# dc-breakout-board.net
KiCad netlist of a schematic drawn in Altium Designer
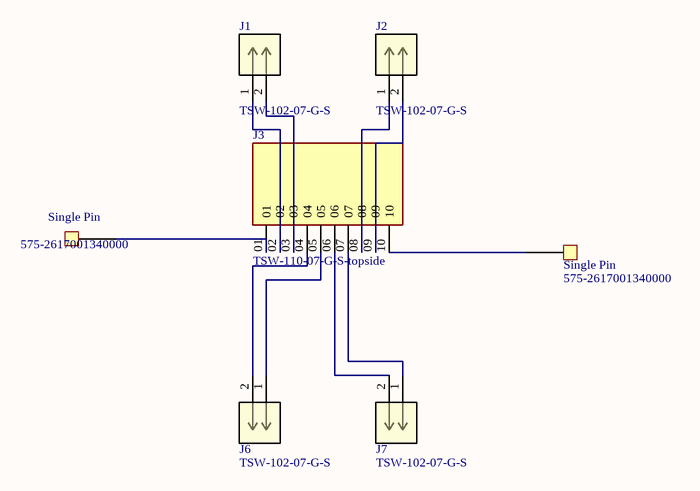
[diagram p0: dc-breakout-board.SchDoc]

(export (version "E")
  (design (tool "Eeschema 10.0.6"))
  (components
    (comp (ref "J1")
      (value "TSW-102-07-G-S")
      (footprint "TSW-102-07-G-S-iceberg")
      (description "No Description Available")
      (fields (field (name "COPYRIGHT") "Copyright (C) 2024 Ultra Librarian. All rights reserved."))
      (libsource (lib "SchlibLafe") (part "TSW-102-07-G-S-iceberg"))
    )
    (comp (ref "J2")
      (value "TSW-102-07-G-S")
      (footprint "TSW-102-07-G-S-iceberg")
      (description "No Description Available")
      (fields (field (name "COPYRIGHT") "Copyright (C) 2024 Ultra Librarian. All rights reserved."))
      (libsource (lib "SchlibLafe") (part "TSW-102-07-G-S-iceberg"))
    )
    (comp (ref "J3")
      (value "TSW-110-07-G-S-topside")
      (footprint "SAMTEC_TSW-110-07-G-S")
      (fields (field (name "MF") "Samtec Inc.") (field (name "MP") "TSW-110-07-G-S"))
      (libsource (lib "SchlibLafe") (part "TSW-110-07-G-S-topside"))
    )
    (comp (ref "J4")
      (value "Single Pin")
      (footprint "Single PC Pin")
      (fields (field (name "SUPPLIER PART NUMBER 1") "575-2617001340000"))
      (libsource (lib "SchlibLafe") (part "Single PC Pin"))
    )
    (comp (ref "J5")
      (value "Single Pin")
      (footprint "Single PC Pin")
      (fields (field (name "SUPPLIER PART NUMBER 1") "575-2617001340000"))
      (libsource (lib "") (part "Single PC Pin_1"))
    )
    (comp (ref "J6")
      (value "TSW-102-07-G-S")
      (footprint "TSW-102-07-G-S-iceberg")
      (description "No Description Available")
      (fields (field (name "COPYRIGHT") "Copyright (C) 2024 Ultra Librarian. All rights reserved."))
      (libsource (lib "") (part "TSW-102-07-G-S-iceberg_1"))
    )
    (comp (ref "J7")
      (value "TSW-102-07-G-S")
      (footprint "TSW-102-07-G-S-iceberg")
      (description "No Description Available")
      (fields (field (name "COPYRIGHT") "Copyright (C) 2024 Ultra Librarian. All rights reserved."))
      (libsource (lib "") (part "TSW-102-07-G-S-iceberg_1"))
    )
  )
  (nets
    (net (code "1") (name "Net-(J1-Pad1)") (class "Default")
      (node (ref "J1") (pin "1") (pinfunction "1_1") (pintype "passive"))
      (node (ref "J3") (pin "02") (pinfunction "02_02") (pintype "passive"))
    )
    (net (code "2") (name "Net-(J1-Pad2)") (class "Default")
      (node (ref "J1") (pin "2") (pinfunction "2_2") (pintype "passive"))
      (node (ref "J3") (pin "03") (pinfunction "03_03") (pintype "passive"))
    )
    (net (code "3") (name "Net-(J2-Pad1)") (class "Default")
      (node (ref "J2") (pin "1") (pinfunction "1_1") (pintype "passive"))
      (node (ref "J3") (pin "08") (pinfunction "08_08") (pintype "passive"))
    )
    (net (code "4") (name "Net-(J2-Pad2)") (class "Default")
      (node (ref "J2") (pin "2") (pinfunction "2_2") (pintype "passive"))
      (node (ref "J3") (pin "09") (pinfunction "09_09") (pintype "passive"))
    )
    (net (code "5") (name "Net-(J3-Pad01)") (class "Default")
      (node (ref "J3") (pin "01") (pinfunction "01_01") (pintype "passive"))
      (node (ref "J4") (pin "1") (pinfunction "1_1") (pintype "passive"))
    )
    (net (code "6") (name "Net-(J3-Pad04)") (class "Default")
      (node (ref "J3") (pin "04") (pinfunction "04_04") (pintype "passive"))
      (node (ref "J6") (pin "2") (pinfunction "2_2") (pintype "passive"))
    )
    (net (code "7") (name "Net-(J3-Pad05)") (class "Default")
      (node (ref "J3") (pin "05") (pinfunction "05_05") (pintype "passive"))
      (node (ref "J6") (pin "1") (pinfunction "1_1") (pintype "passive"))
    )
    (net (code "8") (name "Net-(J3-Pad06)") (class "Default")
      (node (ref "J3") (pin "06") (pinfunction "06_06") (pintype "passive"))
      (node (ref "J7") (pin "2") (pinfunction "2_2") (pintype "passive"))
    )
    (net (code "9") (name "Net-(J3-Pad07)") (class "Default")
      (node (ref "J3") (pin "07") (pinfunction "07_07") (pintype "passive"))
      (node (ref "J7") (pin "1") (pinfunction "1_1") (pintype "passive"))
    )
    (net (code "10") (name "Net-(J3-Pad10)") (class "Default")
      (node (ref "J3") (pin "10") (pinfunction "10_10") (pintype "passive"))
      (node (ref "J5") (pin "1") (pinfunction "1_1") (pintype "passive"))
    )
  )
)
